# Voltage_Regulator.net
KiCad netlist of a schematic drawn in Altium Designer
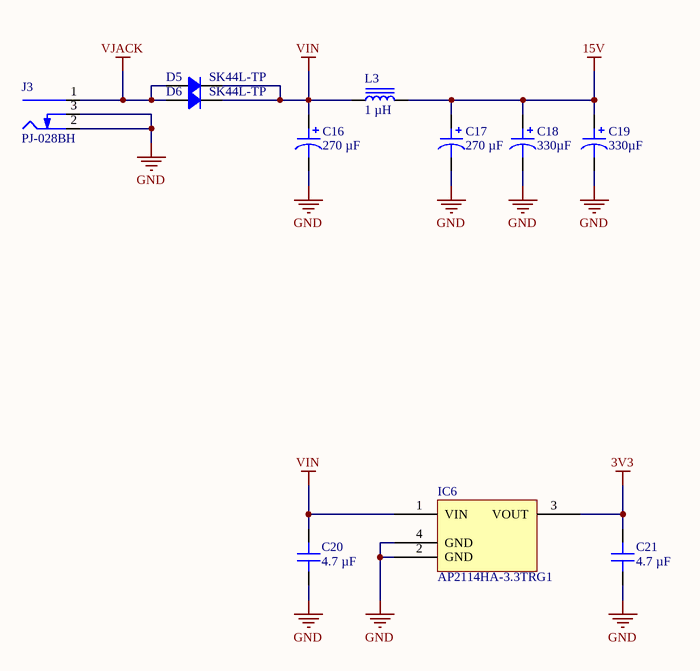
[diagram p0: Voltage Regulator.SchDoc]

(export (version "E")
  (design (tool "Eeschema 10.0.6"))
  (components
    (comp (ref "C16")
      (value "270 µF")
      (footprint "CAP TH ALPOLY D10.00mm S5.00mm H14.00mm")
      (description "CAP ALUM POLY 270UF 20% 35V TH")
      (fields (field (name "PART NUMBER") "A759MU277M1VAAE022") (field (name "MANUFACTURER") "KEMET"))
      (libsource (lib "altiumlibrary.com") (part "Polarised Capacitor"))
    )
    (comp (ref "C17")
      (value "270 µF")
      (footprint "CAP TH ALPOLY D10.00mm S5.00mm H14.00mm")
      (description "CAP ALUM POLY 270UF 20% 35V TH")
      (fields (field (name "PART NUMBER") "A759MU277M1VAAE022") (field (name "MANUFACTURER") "KEMET"))
      (libsource (lib "altiumlibrary.com") (part "Polarised Capacitor"))
    )
    (comp (ref "C18")
      (value "330µF")
      (footprint "CAP TH ALUM ELEC D8.00mm S3.50mm H21.50mm")
      (description "CAP ALUM 330UF 20% 35V THRU HOLE")
      (fields (field (name "PART NUMBER") "860080574014") (field (name "MANUFACTURER") "Würth Elektronik"))
      (libsource (lib "altiumlibrary.com") (part "Polarised Capacitor"))
    )
    (comp (ref "C19")
      (value "330µF")
      (footprint "CAP TH ALUM ELEC D8.00mm S3.50mm H21.50mm")
      (description "CAP ALUM 330UF 20% 35V THRU HOLE")
      (fields (field (name "PART NUMBER") "860080574014") (field (name "MANUFACTURER") "Würth Elektronik"))
      (libsource (lib "altiumlibrary.com") (part "Polarised Capacitor"))
    )
    (comp (ref "C20")
      (value "4.7 µF")
      (footprint "CAP 0805_2012")
      (description "CAP CER 4.7UF 50V X5R 0805")
      (fields
        (field (name "PART NUMBER") "CL21A475KBQNNNE")
        (field (name "MANUFACTURER") "Samsung Electro-Mechanics")
      )
      (libsource (lib "altiumlibrary.com") (part "Capacitor"))
    )
    (comp (ref "C21")
      (value "4.7 µF")
      (footprint "CAP 0805_2012")
      (description "CAP CER 4.7UF 50V X5R 0805")
      (fields
        (field (name "PART NUMBER") "CL21A475KBQNNNE")
        (field (name "MANUFACTURER") "Samsung Electro-Mechanics")
      )
      (libsource (lib "altiumlibrary.com") (part "Capacitor"))
    )
    (comp (ref "D5")
      (value "SK44L-TP")
      (footprint "DO214AB SMC")
      (description "DIODE SCHOTTKY 4A 40V SMC")
      (fields (field (name "MANUFACTURER") "Micro Commercial Co"))
      (libsource (lib "altiumlibrary.com") (part "Diode"))
    )
    (comp (ref "D6")
      (value "SK44L-TP")
      (footprint "DO214AB SMC")
      (description "DIODE SCHOTTKY 4A 40V SMC")
      (fields (field (name "MANUFACTURER") "Micro Commercial Co"))
      (libsource (lib "altiumlibrary.com") (part "Diode"))
    )
    (comp (ref "IC6")
      (value "AP2114HA-3.3TRG1")
      (footprint "DIODES SOT-223")
      (description "IC REG LINEAR 3.3V 1A SOT223")
      (fields (field (name "MANUFACTURER") "Diodes Incorporated"))
      (libsource (lib "altiumlibrary.com") (part "DIODES INC AP2114HA"))
    )
    (comp (ref "J3")
      (value "PJ-028BH")
      (footprint "CUI PJ-028BH")
      (description "CONN POWER JACK 2.5X5.5MM")
      (fields (field (name "MANUFACTURER") "CUI Devices"))
      (libsource (lib "altiumlibrary.com") (part "Barrel Connector"))
    )
    (comp (ref "L3")
      (value "1 µH")
      (footprint "TAIYO YUDEN NRS8030")
      (description "FIXED IND 1UH 6.2A 11.7 MOHM SMD")
      (fields (field (name "PART NUMBER") "NRS8030T1R0NJGJ") (field (name "MANUFACTURER") "Taiyo Yuden"))
      (libsource (lib "altiumlibrary.com") (part "Inductor"))
    )
  )
  (nets
    (net (code "1") (name "3V3") (class "Default")
      (node (ref "C21") (pin "2") (pinfunction "2_2") (pintype "passive"))
      (node (ref "IC6") (pin "3") (pinfunction "VOUT_3") (pintype "passive"))
    )
    (net (code "2") (name "15V") (class "Default")
      (node (ref "C17") (pin "1") (pinfunction "1_1") (pintype "passive"))
      (node (ref "C18") (pin "1") (pinfunction "1_1") (pintype "passive"))
      (node (ref "C19") (pin "1") (pinfunction "1_1") (pintype "passive"))
      (node (ref "L3") (pin "2") (pinfunction "2_2") (pintype "passive"))
    )
    (net (code "3") (name "GND") (class "Default")
      (node (ref "C16") (pin "2") (pinfunction "2_2") (pintype "passive"))
      (node (ref "C17") (pin "2") (pinfunction "2_2") (pintype "passive"))
      (node (ref "C18") (pin "2") (pinfunction "2_2") (pintype "passive"))
      (node (ref "C19") (pin "2") (pinfunction "2_2") (pintype "passive"))
      (node (ref "C20") (pin "1") (pinfunction "1_1") (pintype "passive"))
      (node (ref "C21") (pin "1") (pinfunction "1_1") (pintype "passive"))
      (node (ref "IC6") (pin "2") (pinfunction "GND_2") (pintype "passive"))
      (node (ref "IC6") (pin "4") (pinfunction "GND_4") (pintype "passive"))
      (node (ref "J3") (pin "2") (pinfunction "Outer_2") (pintype "passive"))
      (node (ref "J3") (pin "3") (pinfunction "SW_3") (pintype "passive"))
    )
    (net (code "4") (name "VIN") (class "Default")
      (node (ref "C16") (pin "1") (pinfunction "1_1") (pintype "passive"))
      (node (ref "C20") (pin "2") (pinfunction "2_2") (pintype "passive"))
      (node (ref "D5") (pin "2") (pinfunction "2_2") (pintype "passive"))
      (node (ref "D6") (pin "2") (pinfunction "2_2") (pintype "passive"))
      (node (ref "IC6") (pin "1") (pinfunction "VIN_1") (pintype "passive"))
      (node (ref "L3") (pin "1") (pinfunction "1_1") (pintype "passive"))
    )
    (net (code "5") (name "VJACK") (class "Default")
      (node (ref "D5") (pin "1") (pinfunction "1_1") (pintype "passive"))
      (node (ref "D6") (pin "1") (pinfunction "1_1") (pintype "passive"))
      (node (ref "J3") (pin "1") (pinfunction "Centre_1") (pintype "passive"))
    )
  )
)
